# HEAT_SINK.net
KiCad netlist of a schematic drawn in Altium Designer
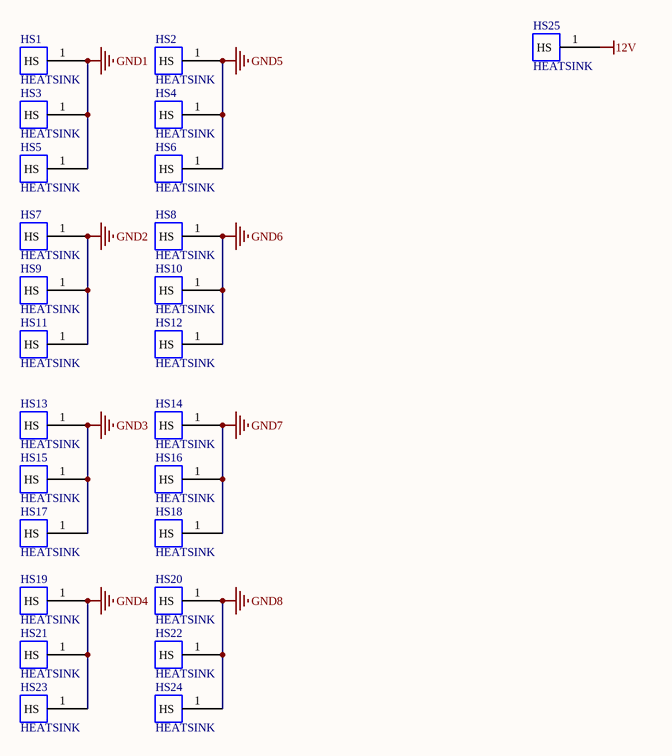
[diagram p0: HEAT_SINK.SchDoc]

(export (version "E")
  (design (tool "Eeschema 10.0.6"))
  (components
    (comp (ref "HS1")
      (value "HEATSINK")
      (footprint "HEAT_SINK")
      (libsource (lib "Miner_8TH") (part "HEAT_SINK"))
    )
    (comp (ref "HS2")
      (value "HEATSINK")
      (footprint "HEAT_SINK")
      (libsource (lib "Miner_8TH") (part "HEAT_SINK"))
    )
    (comp (ref "HS3")
      (value "HEATSINK")
      (footprint "HEAT_SINK")
      (libsource (lib "Miner_8TH") (part "HEAT_SINK"))
    )
    (comp (ref "HS4")
      (value "HEATSINK")
      (footprint "HEAT_SINK")
      (libsource (lib "Miner_8TH") (part "HEAT_SINK"))
    )
    (comp (ref "HS5")
      (value "HEATSINK")
      (footprint "HEAT_SINK")
      (libsource (lib "Miner_8TH") (part "HEAT_SINK"))
    )
    (comp (ref "HS6")
      (value "HEATSINK")
      (footprint "HEAT_SINK")
      (libsource (lib "Miner_8TH") (part "HEAT_SINK"))
    )
    (comp (ref "HS7")
      (value "HEATSINK")
      (footprint "HEAT_SINK")
      (libsource (lib "Miner_8TH") (part "HEAT_SINK"))
    )
    (comp (ref "HS8")
      (value "HEATSINK")
      (footprint "HEAT_SINK")
      (libsource (lib "Miner_8TH") (part "HEAT_SINK"))
    )
    (comp (ref "HS9")
      (value "HEATSINK")
      (footprint "HEAT_SINK")
      (libsource (lib "Miner_8TH") (part "HEAT_SINK"))
    )
    (comp (ref "HS10")
      (value "HEATSINK")
      (footprint "HEAT_SINK")
      (libsource (lib "Miner_8TH") (part "HEAT_SINK"))
    )
    (comp (ref "HS11")
      (value "HEATSINK")
      (footprint "HEAT_SINK")
      (libsource (lib "Miner_8TH") (part "HEAT_SINK"))
    )
    (comp (ref "HS12")
      (value "HEATSINK")
      (footprint "HEAT_SINK")
      (libsource (lib "Miner_8TH") (part "HEAT_SINK"))
    )
    (comp (ref "HS13")
      (value "HEATSINK")
      (footprint "HEAT_SINK")
      (libsource (lib "Miner_8TH") (part "HEAT_SINK"))
    )
    (comp (ref "HS14")
      (value "HEATSINK")
      (footprint "HEAT_SINK")
      (libsource (lib "Miner_8TH") (part "HEAT_SINK"))
    )
    (comp (ref "HS15")
      (value "HEATSINK")
      (footprint "HEAT_SINK")
      (libsource (lib "Miner_8TH") (part "HEAT_SINK"))
    )
    (comp (ref "HS16")
      (value "HEATSINK")
      (footprint "HEAT_SINK")
      (libsource (lib "Miner_8TH") (part "HEAT_SINK"))
    )
    (comp (ref "HS17")
      (value "HEATSINK")
      (footprint "HEAT_SINK")
      (libsource (lib "Miner_8TH") (part "HEAT_SINK"))
    )
    (comp (ref "HS18")
      (value "HEATSINK")
      (footprint "HEAT_SINK")
      (libsource (lib "Miner_8TH") (part "HEAT_SINK"))
    )
    (comp (ref "HS19")
      (value "HEATSINK")
      (footprint "HEAT_SINK")
      (libsource (lib "Miner_8TH") (part "HEAT_SINK"))
    )
    (comp (ref "HS20")
      (value "HEATSINK")
      (footprint "HEAT_SINK")
      (libsource (lib "Miner_8TH") (part "HEAT_SINK"))
    )
    (comp (ref "HS21")
      (value "HEATSINK")
      (footprint "HEAT_SINK")
      (libsource (lib "Miner_8TH") (part "HEAT_SINK"))
    )
    (comp (ref "HS22")
      (value "HEATSINK")
      (footprint "HEAT_SINK")
      (libsource (lib "Miner_8TH") (part "HEAT_SINK"))
    )
    (comp (ref "HS23")
      (value "HEATSINK")
      (footprint "HEAT_SINK")
      (libsource (lib "Miner_8TH") (part "HEAT_SINK"))
    )
    (comp (ref "HS24")
      (value "HEATSINK")
      (footprint "HEAT_SINK")
      (libsource (lib "Miner_8TH") (part "HEAT_SINK"))
    )
    (comp (ref "HS25")
      (value "HEATSINK")
      (footprint "HEAT_SINK")
      (libsource (lib "Miner_8TH") (part "HEAT_SINK"))
    )
  )
  (nets
    (net (code "1") (name "12V") (class "Default")
      (node (ref "HS25") (pin "1") (pinfunction "HS_1") (pintype "passive"))
    )
    (net (code "2") (name "GND1") (class "Default")
      (node (ref "HS1") (pin "1") (pinfunction "HS_1") (pintype "passive"))
      (node (ref "HS3") (pin "1") (pinfunction "HS_1") (pintype "passive"))
      (node (ref "HS5") (pin "1") (pinfunction "HS_1") (pintype "passive"))
    )
    (net (code "3") (name "GND2") (class "Default")
      (node (ref "HS11") (pin "1") (pinfunction "HS_1") (pintype "passive"))
      (node (ref "HS7") (pin "1") (pinfunction "HS_1") (pintype "passive"))
      (node (ref "HS9") (pin "1") (pinfunction "HS_1") (pintype "passive"))
    )
    (net (code "4") (name "GND3") (class "Default")
      (node (ref "HS13") (pin "1") (pinfunction "HS_1") (pintype "passive"))
      (node (ref "HS15") (pin "1") (pinfunction "HS_1") (pintype "passive"))
      (node (ref "HS17") (pin "1") (pinfunction "HS_1") (pintype "passive"))
    )
    (net (code "5") (name "GND4") (class "Default")
      (node (ref "HS19") (pin "1") (pinfunction "HS_1") (pintype "passive"))
      (node (ref "HS21") (pin "1") (pinfunction "HS_1") (pintype "passive"))
      (node (ref "HS23") (pin "1") (pinfunction "HS_1") (pintype "passive"))
    )
    (net (code "6") (name "GND5") (class "Default")
      (node (ref "HS2") (pin "1") (pinfunction "HS_1") (pintype "passive"))
      (node (ref "HS4") (pin "1") (pinfunction "HS_1") (pintype "passive"))
      (node (ref "HS6") (pin "1") (pinfunction "HS_1") (pintype "passive"))
    )
    (net (code "7") (name "GND6") (class "Default")
      (node (ref "HS10") (pin "1") (pinfunction "HS_1") (pintype "passive"))
      (node (ref "HS12") (pin "1") (pinfunction "HS_1") (pintype "passive"))
      (node (ref "HS8") (pin "1") (pinfunction "HS_1") (pintype "passive"))
    )
    (net (code "8") (name "GND7") (class "Default")
      (node (ref "HS14") (pin "1") (pinfunction "HS_1") (pintype "passive"))
      (node (ref "HS16") (pin "1") (pinfunction "HS_1") (pintype "passive"))
      (node (ref "HS18") (pin "1") (pinfunction "HS_1") (pintype "passive"))
    )
    (net (code "9") (name "GND8") (class "Default")
      (node (ref "HS20") (pin "1") (pinfunction "HS_1") (pintype "passive"))
      (node (ref "HS22") (pin "1") (pinfunction "HS_1") (pintype "passive"))
      (node (ref "HS24") (pin "1") (pinfunction "HS_1") (pintype "passive"))
    )
  )
)
